# pogo-org.net
KiCad netlist of a schematic drawn in EAGLE
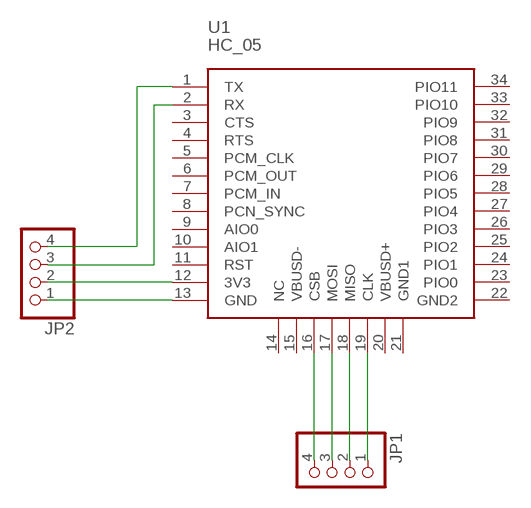
[diagram p0: schematic, sheet 1]

(export (version "E")
  (design (tool "Eeschema 10.0.6"))
  (components
    (comp (ref "JP1")
      (value "PINHD-1X4")
      (footprint "eagle-import:1X04")
      (libsource (lib "eagle-import") (part "PINHD-1X4"))
    )
    (comp (ref "JP2")
      (value "PINHD-1X4")
      (footprint "eagle-import:1X04")
      (libsource (lib "eagle-import") (part "PINHD-1X4"))
    )
    (comp (ref "U1")
      (value "HC_05")
      (footprint "eagle-import:BLUETOOTH_SMD")
      (libsource (lib "eagle-import") (part "HC_05"))
    )
  )
  (nets
    (net (code "1") (name "Net-(U1-3V3)") (class "Default")
      (node (ref "JP2") (pin "2") (pinfunction "2_2") (pintype "passive"))
      (node (ref "U1") (pin "12") (pinfunction "3V3_12") (pintype "bidirectional"))
    )
    (net (code "2") (name "Net-(U1-CLK)") (class "Default")
      (node (ref "JP1") (pin "1") (pinfunction "1_1") (pintype "passive"))
      (node (ref "U1") (pin "19") (pinfunction "CLK_19") (pintype "bidirectional"))
    )
    (net (code "3") (name "Net-(U1-CSB)") (class "Default")
      (node (ref "JP1") (pin "4") (pinfunction "4_4") (pintype "passive"))
      (node (ref "U1") (pin "16") (pinfunction "CSB_16") (pintype "bidirectional"))
    )
    (net (code "4") (name "Net-(U1-GND)") (class "Default")
      (node (ref "JP2") (pin "1") (pinfunction "1_1") (pintype "passive"))
      (node (ref "U1") (pin "13") (pinfunction "GND_13") (pintype "bidirectional"))
    )
    (net (code "5") (name "Net-(U1-MISO)") (class "Default")
      (node (ref "JP1") (pin "2") (pinfunction "2_2") (pintype "passive"))
      (node (ref "U1") (pin "18") (pinfunction "MISO_18") (pintype "bidirectional"))
    )
    (net (code "6") (name "Net-(U1-MOSI)") (class "Default")
      (node (ref "JP1") (pin "3") (pinfunction "3_3") (pintype "passive"))
      (node (ref "U1") (pin "17") (pinfunction "MOSI_17") (pintype "bidirectional"))
    )
    (net (code "7") (name "Net-(U1-RX)") (class "Default")
      (node (ref "JP2") (pin "3") (pinfunction "3_3") (pintype "passive"))
      (node (ref "U1") (pin "2") (pinfunction "RX_2") (pintype "bidirectional"))
    )
    (net (code "8") (name "Net-(U1-TX)") (class "Default")
      (node (ref "JP2") (pin "4") (pinfunction "4_4") (pintype "passive"))
      (node (ref "U1") (pin "1") (pinfunction "TX_1") (pintype "bidirectional"))
    )
    (net (code "9") (name "unconnected-(U1-AIO0-Pad9)") (class "Default")
      (node (ref "U1") (pin "9") (pinfunction "AIO0_9") (pintype "bidirectional"))
    )
    (net (code "10") (name "unconnected-(U1-AIO1-Pad10)") (class "Default")
      (node (ref "U1") (pin "10") (pinfunction "AIO1_10") (pintype "bidirectional"))
    )
    (net (code "11") (name "unconnected-(U1-CTS-Pad3)") (class "Default")
      (node (ref "U1") (pin "3") (pinfunction "CTS_3") (pintype "bidirectional"))
    )
    (net (code "12") (name "unconnected-(U1-GND1-Pad21)") (class "Default")
      (node (ref "U1") (pin "21") (pinfunction "GND1_21") (pintype "bidirectional"))
    )
    (net (code "13") (name "unconnected-(U1-GND2-Pad22)") (class "Default")
      (node (ref "U1") (pin "22") (pinfunction "GND2_22") (pintype "bidirectional"))
    )
    (net (code "14") (name "unconnected-(U1-NC-Pad14)") (class "Default")
      (node (ref "U1") (pin "14") (pinfunction "NC_14") (pintype "bidirectional"))
    )
    (net (code "15") (name "unconnected-(U1-PCM_CLK-Pad5)") (class "Default")
      (node (ref "U1") (pin "5") (pinfunction "PCM_CLK_5") (pintype "bidirectional"))
    )
    (net (code "16") (name "unconnected-(U1-PCM_IN-Pad7)") (class "Default")
      (node (ref "U1") (pin "7") (pinfunction "PCM_IN_7") (pintype "bidirectional"))
    )
    (net (code "17") (name "unconnected-(U1-PCM_OUT-Pad6)") (class "Default")
      (node (ref "U1") (pin "6") (pinfunction "PCM_OUT_6") (pintype "bidirectional"))
    )
    (net (code "18") (name "unconnected-(U1-PCN_SYNC-Pad8)") (class "Default")
      (node (ref "U1") (pin "8") (pinfunction "PCN_SYNC_8") (pintype "bidirectional"))
    )
    (net (code "19") (name "unconnected-(U1-PIO0-Pad23)") (class "Default")
      (node (ref "U1") (pin "23") (pinfunction "PIO0_23") (pintype "bidirectional"))
    )
    (net (code "20") (name "unconnected-(U1-PIO1-Pad24)") (class "Default")
      (node (ref "U1") (pin "24") (pinfunction "PIO1_24") (pintype "bidirectional"))
    )
    (net (code "21") (name "unconnected-(U1-PIO2-Pad25)") (class "Default")
      (node (ref "U1") (pin "25") (pinfunction "PIO2_25") (pintype "bidirectional"))
    )
    (net (code "22") (name "unconnected-(U1-PIO3-Pad26)") (class "Default")
      (node (ref "U1") (pin "26") (pinfunction "PIO3_26") (pintype "bidirectional"))
    )
    (net (code "23") (name "unconnected-(U1-PIO4-Pad27)") (class "Default")
      (node (ref "U1") (pin "27") (pinfunction "PIO4_27") (pintype "bidirectional"))
    )
    (net (code "24") (name "unconnected-(U1-PIO5-Pad28)") (class "Default")
      (node (ref "U1") (pin "28") (pinfunction "PIO5_28") (pintype "bidirectional"))
    )
    (net (code "25") (name "unconnected-(U1-PIO6-Pad29)") (class "Default")
      (node (ref "U1") (pin "29") (pinfunction "PIO6_29") (pintype "bidirectional"))
    )
    (net (code "26") (name "unconnected-(U1-PIO7-Pad30)") (class "Default")
      (node (ref "U1") (pin "30") (pinfunction "PIO7_30") (pintype "bidirectional"))
    )
    (net (code "27") (name "unconnected-(U1-PIO8-Pad31)") (class "Default")
      (node (ref "U1") (pin "31") (pinfunction "PIO8_31") (pintype "bidirectional"))
    )
    (net (code "28") (name "unconnected-(U1-PIO9-Pad32)") (class "Default")
      (node (ref "U1") (pin "32") (pinfunction "PIO9_32") (pintype "bidirectional"))
    )
    (net (code "29") (name "unconnected-(U1-PIO10-Pad33)") (class "Default")
      (node (ref "U1") (pin "33") (pinfunction "PIO10_33") (pintype "bidirectional"))
    )
    (net (code "30") (name "unconnected-(U1-PIO11-Pad34)") (class "Default")
      (node (ref "U1") (pin "34") (pinfunction "PIO11_34") (pintype "bidirectional"))
    )
    (net (code "31") (name "unconnected-(U1-RST-Pad11)") (class "Default")
      (node (ref "U1") (pin "11") (pinfunction "RST_11") (pintype "bidirectional"))
    )
    (net (code "32") (name "unconnected-(U1-RTS-Pad4)") (class "Default")
      (node (ref "U1") (pin "4") (pinfunction "RTS_4") (pintype "bidirectional"))
    )
    (net (code "33") (name "unconnected-(U1-VBUSD+-Pad20)") (class "Default")
      (node (ref "U1") (pin "20") (pinfunction "VBUSD+_20") (pintype "bidirectional"))
    )
    (net (code "34") (name "unconnected-(U1-VBUSD--Pad15)") (class "Default")
      (node (ref "U1") (pin "15") (pinfunction "VBUSD-_15") (pintype "bidirectional"))
    )
  )
)
